# shift_registers.net
KiCad netlist of a schematic drawn in Altium Designer
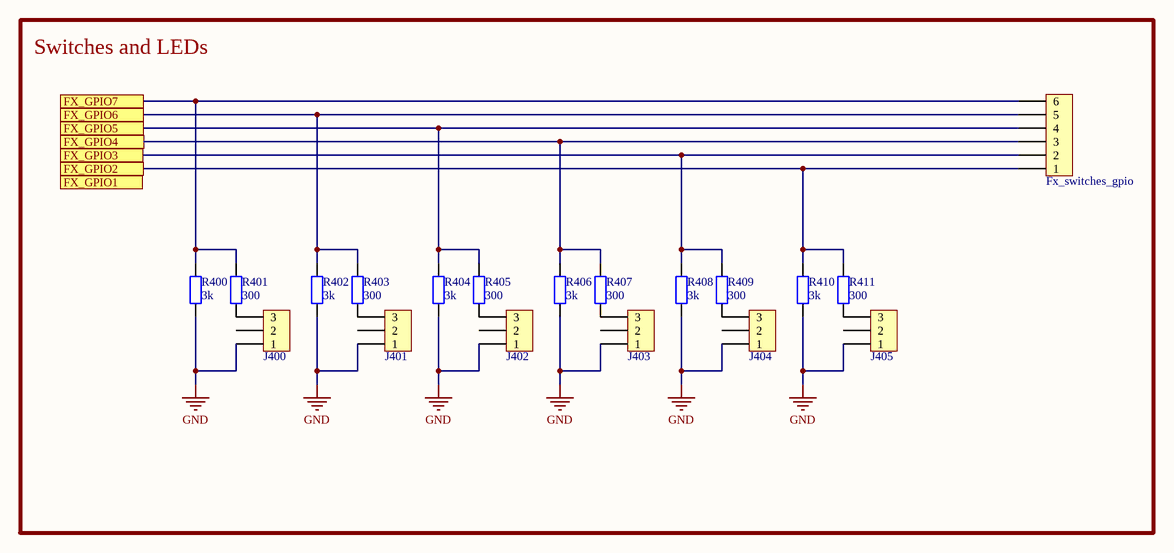
[diagram p0: shift_registers.SchDoc]

(export (version "E")
  (design (tool "Eeschema 10.0.6"))
  (components
    (comp (ref "Fx_switches_gpio")
      (value "Header 1x6")
      (footprint "Header 1x6")
      (libsource (lib "AAURacing") (part "Header 1x6"))
    )
    (comp (ref "J400")
      (value "Header 1x3")
      (footprint "Header 1x3")
      (libsource (lib "AAURacing") (part "Header 1x3"))
    )
    (comp (ref "J401")
      (value "Header 1x3")
      (footprint "Header 1x3")
      (libsource (lib "AAURacing") (part "Header 1x3"))
    )
    (comp (ref "J402")
      (value "Header 1x3")
      (footprint "Header 1x3")
      (libsource (lib "AAURacing") (part "Header 1x3"))
    )
    (comp (ref "J403")
      (value "Header 1x3")
      (footprint "Header 1x3")
      (libsource (lib "AAURacing") (part "Header 1x3"))
    )
    (comp (ref "J404")
      (value "Header 1x3")
      (footprint "Header 1x3")
      (libsource (lib "AAURacing") (part "Header 1x3"))
    )
    (comp (ref "J405")
      (value "Header 1x3")
      (footprint "Header 1x3")
      (libsource (lib "AAURacing") (part "Header 1x3"))
    )
    (comp (ref "R400")
      (value "3k")
      (footprint "AXIAL-0.4 PCBK")
      (description "Resistor")
      (fields (field (name "PUBLISHER") "Altium Limited"))
      (libsource (lib "pcb_kursus_lib2020 (1)") (part "Res PCBK"))
    )
    (comp (ref "R401")
      (value "300")
      (footprint "AXIAL-0.4 PCBK")
      (description "Resistor")
      (fields (field (name "PUBLISHER") "Altium Limited"))
      (libsource (lib "pcb_kursus_lib2020 (1)") (part "Res PCBK"))
    )
    (comp (ref "R402")
      (value "3k")
      (footprint "AXIAL-0.4 PCBK")
      (description "Resistor")
      (fields (field (name "PUBLISHER") "Altium Limited"))
      (libsource (lib "pcb_kursus_lib2020 (1)") (part "Res PCBK"))
    )
    (comp (ref "R403")
      (value "300")
      (footprint "AXIAL-0.4 PCBK")
      (description "Resistor")
      (fields (field (name "PUBLISHER") "Altium Limited"))
      (libsource (lib "pcb_kursus_lib2020 (1)") (part "Res PCBK"))
    )
    (comp (ref "R404")
      (value "3k")
      (footprint "AXIAL-0.4 PCBK")
      (description "Resistor")
      (fields (field (name "PUBLISHER") "Altium Limited"))
      (libsource (lib "pcb_kursus_lib2020 (1)") (part "Res PCBK"))
    )
    (comp (ref "R405")
      (value "300")
      (footprint "AXIAL-0.4 PCBK")
      (description "Resistor")
      (fields (field (name "PUBLISHER") "Altium Limited"))
      (libsource (lib "pcb_kursus_lib2020 (1)") (part "Res PCBK"))
    )
    (comp (ref "R406")
      (value "3k")
      (footprint "AXIAL-0.4 PCBK")
      (description "Resistor")
      (fields (field (name "PUBLISHER") "Altium Limited"))
      (libsource (lib "pcb_kursus_lib2020 (1)") (part "Res PCBK"))
    )
    (comp (ref "R407")
      (value "300")
      (footprint "AXIAL-0.4 PCBK")
      (description "Resistor")
      (fields (field (name "PUBLISHER") "Altium Limited"))
      (libsource (lib "pcb_kursus_lib2020 (1)") (part "Res PCBK"))
    )
    (comp (ref "R408")
      (value "3k")
      (footprint "AXIAL-0.4 PCBK")
      (description "Resistor")
      (fields (field (name "PUBLISHER") "Altium Limited"))
      (libsource (lib "pcb_kursus_lib2020 (1)") (part "Res PCBK"))
    )
    (comp (ref "R409")
      (value "300")
      (footprint "AXIAL-0.4 PCBK")
      (description "Resistor")
      (fields (field (name "PUBLISHER") "Altium Limited"))
      (libsource (lib "pcb_kursus_lib2020 (1)") (part "Res PCBK"))
    )
    (comp (ref "R410")
      (value "3k")
      (footprint "AXIAL-0.4 PCBK")
      (description "Resistor")
      (fields (field (name "PUBLISHER") "Altium Limited"))
      (libsource (lib "pcb_kursus_lib2020 (1)") (part "Res PCBK"))
    )
    (comp (ref "R411")
      (value "300")
      (footprint "AXIAL-0.4 PCBK")
      (description "Resistor")
      (fields (field (name "PUBLISHER") "Altium Limited"))
      (libsource (lib "pcb_kursus_lib2020 (1)") (part "Res PCBK"))
    )
  )
  (nets
    (net (code "4") (name "/FX_GPIO2") (class "Default")
      (node (ref "Fx_switches_gpio") (pin "1") (pinfunction "1_1") (pintype "passive"))
      (node (ref "R410") (pin "2") (pinfunction "2_2") (pintype "passive"))
      (node (ref "R411") (pin "2") (pinfunction "2_2") (pintype "passive"))
    )
    (net (code "5") (name "/FX_GPIO3") (class "Default")
      (node (ref "Fx_switches_gpio") (pin "2") (pinfunction "2_2") (pintype "passive"))
      (node (ref "R408") (pin "2") (pinfunction "2_2") (pintype "passive"))
      (node (ref "R409") (pin "2") (pinfunction "2_2") (pintype "passive"))
    )
    (net (code "6") (name "/FX_GPIO4") (class "Default")
      (node (ref "Fx_switches_gpio") (pin "3") (pinfunction "3_3") (pintype "passive"))
      (node (ref "R406") (pin "2") (pinfunction "2_2") (pintype "passive"))
      (node (ref "R407") (pin "2") (pinfunction "2_2") (pintype "passive"))
    )
    (net (code "7") (name "/FX_GPIO5") (class "Default")
      (node (ref "Fx_switches_gpio") (pin "4") (pinfunction "4_4") (pintype "passive"))
      (node (ref "R404") (pin "2") (pinfunction "2_2") (pintype "passive"))
      (node (ref "R405") (pin "2") (pinfunction "2_2") (pintype "passive"))
    )
    (net (code "8") (name "/FX_GPIO6") (class "Default")
      (node (ref "Fx_switches_gpio") (pin "5") (pinfunction "5_5") (pintype "passive"))
      (node (ref "R402") (pin "2") (pinfunction "2_2") (pintype "passive"))
      (node (ref "R403") (pin "2") (pinfunction "2_2") (pintype "passive"))
    )
    (net (code "9") (name "/FX_GPIO7") (class "Default")
      (node (ref "Fx_switches_gpio") (pin "6") (pinfunction "6_6") (pintype "passive"))
      (node (ref "R400") (pin "2") (pinfunction "2_2") (pintype "passive"))
      (node (ref "R401") (pin "2") (pinfunction "2_2") (pintype "passive"))
    )
    (net (code "10") (name "GND") (class "Default")
      (node (ref "J400") (pin "1") (pinfunction "1_1") (pintype "passive"))
      (node (ref "J401") (pin "1") (pinfunction "1_1") (pintype "passive"))
      (node (ref "J402") (pin "1") (pinfunction "1_1") (pintype "passive"))
      (node (ref "J403") (pin "1") (pinfunction "1_1") (pintype "passive"))
      (node (ref "J404") (pin "1") (pinfunction "1_1") (pintype "passive"))
      (node (ref "J405") (pin "1") (pinfunction "1_1") (pintype "passive"))
      (node (ref "R400") (pin "1") (pinfunction "1_1") (pintype "passive"))
      (node (ref "R402") (pin "1") (pinfunction "1_1") (pintype "passive"))
      (node (ref "R404") (pin "1") (pinfunction "1_1") (pintype "passive"))
      (node (ref "R406") (pin "1") (pinfunction "1_1") (pintype "passive"))
      (node (ref "R408") (pin "1") (pinfunction "1_1") (pintype "passive"))
      (node (ref "R410") (pin "1") (pinfunction "1_1") (pintype "passive"))
    )
    (net (code "11") (name "Net-(J400-Pad3)") (class "Default")
      (node (ref "J400") (pin "3") (pinfunction "3_3") (pintype "passive"))
      (node (ref "R401") (pin "1") (pinfunction "1_1") (pintype "passive"))
    )
    (net (code "12") (name "Net-(J401-Pad3)") (class "Default")
      (node (ref "J401") (pin "3") (pinfunction "3_3") (pintype "passive"))
      (node (ref "R403") (pin "1") (pinfunction "1_1") (pintype "passive"))
    )
    (net (code "13") (name "Net-(J402-Pad3)") (class "Default")
      (node (ref "J402") (pin "3") (pinfunction "3_3") (pintype "passive"))
      (node (ref "R405") (pin "1") (pinfunction "1_1") (pintype "passive"))
    )
    (net (code "14") (name "Net-(J403-Pad3)") (class "Default")
      (node (ref "J403") (pin "3") (pinfunction "3_3") (pintype "passive"))
      (node (ref "R407") (pin "1") (pinfunction "1_1") (pintype "passive"))
    )
    (net (code "15") (name "Net-(J404-Pad3)") (class "Default")
      (node (ref "J404") (pin "3") (pinfunction "3_3") (pintype "passive"))
      (node (ref "R409") (pin "1") (pinfunction "1_1") (pintype "passive"))
    )
    (net (code "16") (name "Net-(J405-Pad3)") (class "Default")
      (node (ref "J405") (pin "3") (pinfunction "3_3") (pintype "passive"))
      (node (ref "R411") (pin "1") (pinfunction "1_1") (pintype "passive"))
    )
    (net (code "17") (name "unconnected-(J400-Pad2)") (class "Default")
      (node (ref "J400") (pin "2") (pinfunction "2_2") (pintype "passive"))
    )
    (net (code "18") (name "unconnected-(J401-Pad2)") (class "Default")
      (node (ref "J401") (pin "2") (pinfunction "2_2") (pintype "passive"))
    )
    (net (code "19") (name "unconnected-(J402-Pad2)") (class "Default")
      (node (ref "J402") (pin "2") (pinfunction "2_2") (pintype "passive"))
    )
    (net (code "20") (name "unconnected-(J403-Pad2)") (class "Default")
      (node (ref "J403") (pin "2") (pinfunction "2_2") (pintype "passive"))
    )
    (net (code "21") (name "unconnected-(J404-Pad2)") (class "Default")
      (node (ref "J404") (pin "2") (pinfunction "2_2") (pintype "passive"))
    )
    (net (code "22") (name "unconnected-(J405-Pad2)") (class "Default")
      (node (ref "J405") (pin "2") (pinfunction "2_2") (pintype "passive"))
    )
  )
)
